# PrototypeBoardV2C.net
KiCad netlist of a schematic drawn in EasyEDA Pro
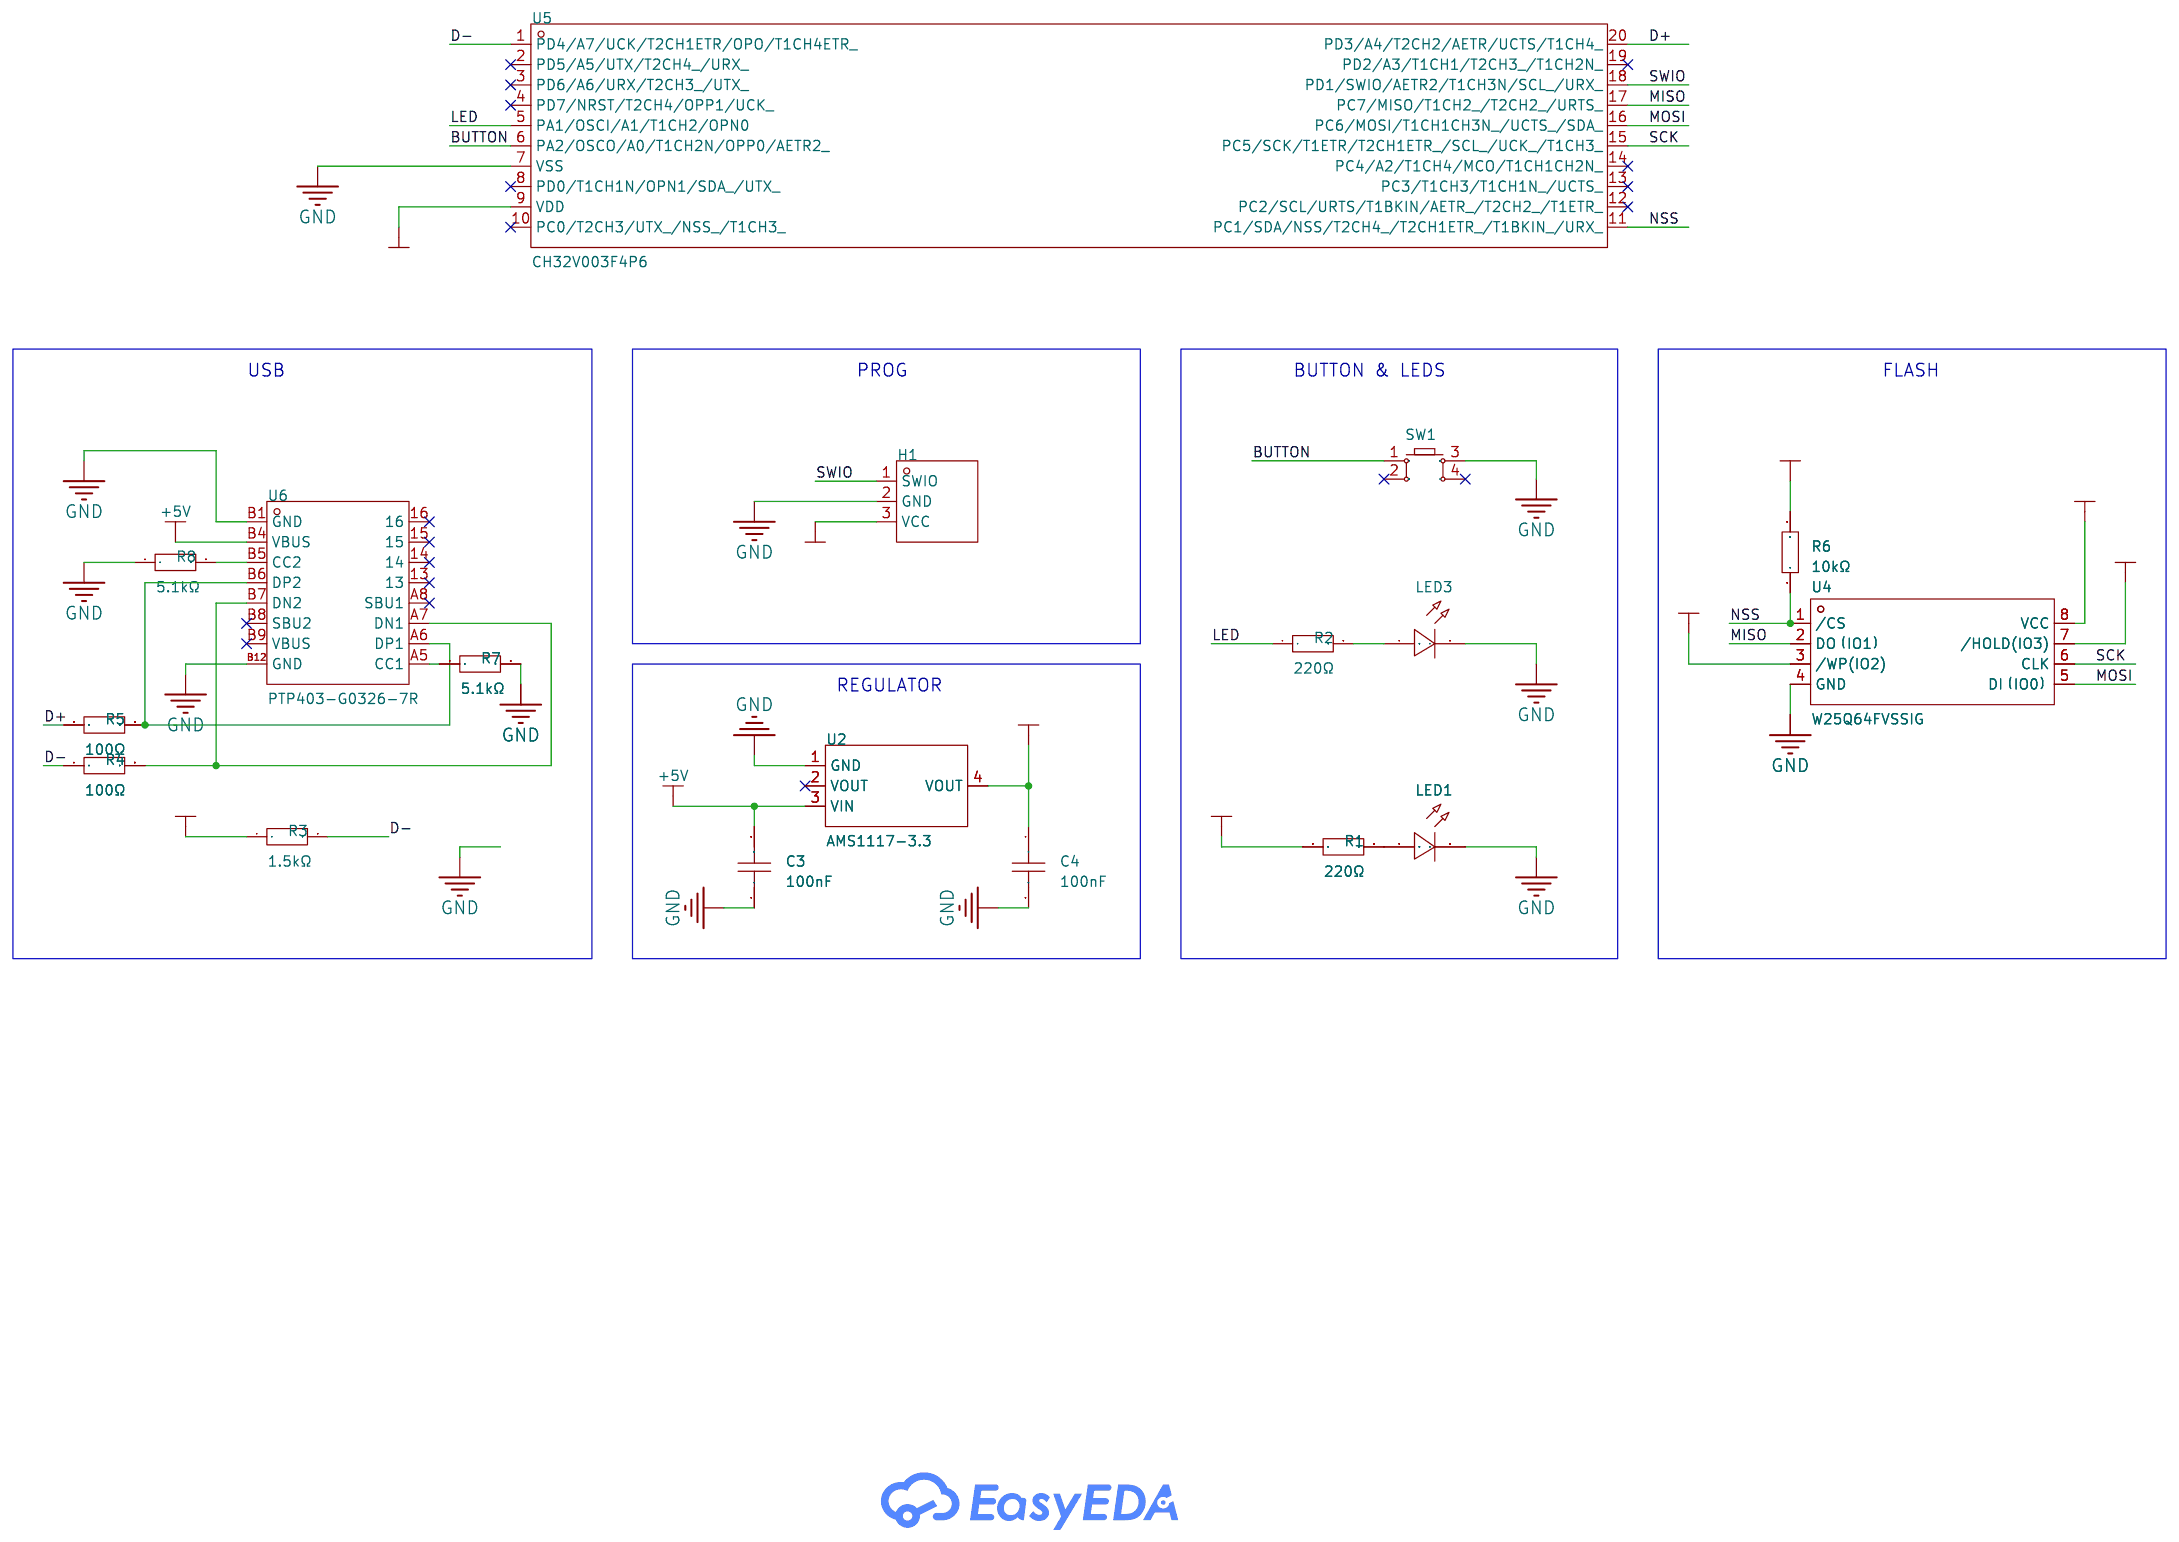
[diagram p0: schematic sheet]

(export (version "E")
  (design (tool "Eeschema 10.0.6"))
  (components
    (comp (ref "C3")
      (value "100nF")
      (footprint "easyedapro:CAP-TH_L5.8-W3.0-P4.7-D0.45")
      (fields (field (name "Manufacturer Part") "1C10Z5U104M050B") (field (name "Manufacturer") "VISHAY(威世)"))
      (libsource (lib "easyedapro") (part "1C10Z5U104M050B"))
    )
    (comp (ref "C4")
      (value "100nF")
      (footprint "easyedapro:CAP-TH_L5.8-W3.0-P4.7-D0.45")
      (fields (field (name "Manufacturer Part") "1C10Z5U104M050B") (field (name "Manufacturer") "VISHAY(威世)"))
      (libsource (lib "easyedapro") (part "1C10Z5U104M050B"))
    )
    (comp (ref "H1")
      (value "~")
      (footprint "easyedapro:HDR-TH_3P-P2.54-V-M")
      (libsource (lib "easyedapro") (part "PZ254V-11-03P_C2937625"))
    )
    (comp (ref "LED1")
      (value "~")
      (footprint "easyedapro:LED-TH_BD3.0-P2.54-FD")
      (libsource (lib "easyedapro") (part "LED_TH-R"))
    )
    (comp (ref "LED3")
      (value "~")
      (footprint "easyedapro:LED-TH_BD5.0-P2.54-L-RD_WHITE")
      (libsource (lib "easyedapro") (part "LED_TH-B"))
    )
    (comp (ref "R1")
      (value "220Ω")
      (footprint "easyedapro:RES-TH_BD1.8-L3.2-P7.20-D0.4")
      (libsource (lib "easyedapro") (part "Res"))
    )
    (comp (ref "R2")
      (value "220Ω")
      (footprint "easyedapro:RES-TH_BD1.8-L3.2-P7.20-D0.4")
      (libsource (lib "easyedapro") (part "Res"))
    )
    (comp (ref "R3")
      (value "1.5kΩ")
      (footprint "easyedapro:RES-TH_BD1.8-L3.2-P7.20-D0.4")
      (libsource (lib "easyedapro") (part "Res"))
    )
    (comp (ref "R4")
      (value "100Ω")
      (footprint "easyedapro:RES-TH_BD1.8-L3.2-P7.20-D0.4")
      (libsource (lib "easyedapro") (part "Res"))
    )
    (comp (ref "R5")
      (value "100Ω")
      (footprint "easyedapro:RES-TH_BD1.8-L3.2-P7.20-D0.4")
      (libsource (lib "easyedapro") (part "Res"))
    )
    (comp (ref "R6")
      (value "10kΩ")
      (footprint "easyedapro:RES-TH_BD1.8-L3.2-P7.20-D0.4")
      (libsource (lib "easyedapro") (part "Res"))
    )
    (comp (ref "R7")
      (value "5.1kΩ")
      (footprint "easyedapro:RES-TH_BD1.8-L3.2-P7.20-D0.4")
      (libsource (lib "easyedapro") (part "Res"))
    )
    (comp (ref "R8")
      (value "5.1kΩ")
      (footprint "easyedapro:RES-TH_BD1.8-L3.2-P7.20-D0.4")
      (libsource (lib "easyedapro") (part "Res"))
    )
    (comp (ref "SW1")
      (value "~")
      (footprint "easyedapro:KEY-TH_4P-L6.0-W6.0-P3.90-LS6.5")
      (libsource (lib "easyedapro") (part "轻触按键"))
    )
    (comp (ref "U2")
      (value "AMS1117-3.3")
      (footprint "easyedapro:SOT-223-3_L6.5-W3.4-P2.30-LS7.0-BR")
      (fields (field (name "Manufacturer") "AMS"))
      (libsource (lib "easyedapro") (part "AMS1117-3.3"))
    )
    (comp (ref "U4")
      (value "W25Q64FVSSIG")
      (footprint "easyedapro:SOIC-8_L5.3-W5.3-P1.27-LS8.0-BL")
      (libsource (lib "easyedapro") (part "W25Q64FVSSIG_C66141"))
    )
    (comp (ref "U5")
      (value "CH32V003F4P6")
      (footprint "easyedapro:TSSOP-20_L6.5-W4.4-P0.65-LS6.4-BL")
      (fields (field (name "Manufacturer") "WCH(南京沁恒)"))
      (libsource (lib "easyedapro") (part "CH32V003F4P6"))
    )
    (comp (ref "U6")
      (value "PTP403-G0326-7R")
      (footprint "easyedapro:USB-SMD_PTP403-G0326-7R")
      (libsource (lib "easyedapro") (part "PTP403-G0326-7R"))
    )
  )
  (nets
    (net (code "1") (name "+3.3V") (class "Default")
      (node (ref "C4") (pin "1") (pinfunction "1_1") (pintype "unspecified"))
      (node (ref "H1") (pin "3") (pinfunction "VCC_3") (pintype "unspecified"))
      (node (ref "R1") (pin "1") (pinfunction "1_1") (pintype "input"))
      (node (ref "R3") (pin "1") (pinfunction "1_1") (pintype "input"))
      (node (ref "R6") (pin "2") (pinfunction "2_2") (pintype "input"))
      (node (ref "U2") (pin "4") (pinfunction "VOUT_4") (pintype "unspecified"))
      (node (ref "U4") (pin "3") (pinfunction "/WP(IO2)_3") (pintype "unspecified"))
      (node (ref "U4") (pin "7") (pinfunction "/HOLD(IO3)_7") (pintype "unspecified"))
      (node (ref "U4") (pin "8") (pinfunction "VCC_8") (pintype "unspecified"))
      (node (ref "U5") (pin "9") (pinfunction "VDD_9") (pintype "unspecified"))
    )
    (net (code "2") (name "+5V") (class "Default")
      (node (ref "C3") (pin "2") (pinfunction "2_2") (pintype "unspecified"))
      (node (ref "U2") (pin "3") (pinfunction "VIN_3") (pintype "unspecified"))
      (node (ref "U6") (pin "B4") (pinfunction "VBUS_B4") (pintype "input"))
    )
    (net (code "3") (name "/BUTTON") (class "Default")
      (node (ref "SW1") (pin "1") (pinfunction "1_1") (pintype "input"))
      (node (ref "U5") (pin "6") (pinfunction "PA2/OSCO/A0/T1CH2N/OPP0/AETR2__6") (pintype "unspecified"))
    )
    (net (code "4") (name "/D+") (class "Default")
      (node (ref "R5") (pin "1") (pinfunction "1_1") (pintype "input"))
      (node (ref "U5") (pin "20") (pinfunction "PD3/A4/T2CH2/AETR/UCTS/T1CH4__20") (pintype "unspecified"))
    )
    (net (code "5") (name "/D-") (class "Default")
      (node (ref "R3") (pin "2") (pinfunction "2_2") (pintype "input"))
      (node (ref "R4") (pin "1") (pinfunction "1_1") (pintype "input"))
      (node (ref "U5") (pin "1") (pinfunction "PD4/A7/UCK/T2CH1ETR/OPO/T1CH4ETR__1") (pintype "unspecified"))
    )
    (net (code "6") (name "/LED") (class "Default")
      (node (ref "R2") (pin "1") (pinfunction "1_1") (pintype "input"))
      (node (ref "U5") (pin "5") (pinfunction "PA1/OSCI/A1/T1CH2/OPN0_5") (pintype "unspecified"))
    )
    (net (code "7") (name "/MISO") (class "Default")
      (node (ref "U4") (pin "2") (pinfunction "DO（IO1）_2") (pintype "unspecified"))
      (node (ref "U5") (pin "17") (pinfunction "PC7/MISO/T1CH2_/T2CH2_/URTS__17") (pintype "unspecified"))
    )
    (net (code "8") (name "/MOSI") (class "Default")
      (node (ref "U4") (pin "5") (pinfunction "DI（IO0）_5") (pintype "unspecified"))
      (node (ref "U5") (pin "16") (pinfunction "PC6/MOSI/T1CH1CH3N_/UCTS_/SDA__16") (pintype "unspecified"))
    )
    (net (code "9") (name "/NSS") (class "Default")
      (node (ref "R6") (pin "1") (pinfunction "1_1") (pintype "input"))
      (node (ref "U4") (pin "1") (pinfunction "/CS_1") (pintype "unspecified"))
      (node (ref "U5") (pin "11") (pinfunction "PC1/SDA/NSS/T2CH4_/T2CH1ETR_/T1BKIN_/URX__11") (pintype "unspecified"))
    )
    (net (code "10") (name "/SCK") (class "Default")
      (node (ref "U4") (pin "6") (pinfunction "CLK_6") (pintype "unspecified"))
      (node (ref "U5") (pin "15") (pinfunction "PC5/SCK/T1ETR/T2CH1ETR_/SCL_/UCK_/T1CH3__15") (pintype "unspecified"))
    )
    (net (code "11") (name "/SWIO") (class "Default")
      (node (ref "H1") (pin "1") (pinfunction "SWIO_1") (pintype "unspecified"))
      (node (ref "U5") (pin "18") (pinfunction "PD1/SWIO/AETR2/T1CH3N/SCL_/URX__18") (pintype "unspecified"))
    )
    (net (code "12") (name "GND") (class "Default")
      (node (ref "C3") (pin "1") (pinfunction "1_1") (pintype "unspecified"))
      (node (ref "C4") (pin "2") (pinfunction "2_2") (pintype "unspecified"))
      (node (ref "H1") (pin "2") (pinfunction "GND_2") (pintype "unspecified"))
      (node (ref "LED1") (pin "2") (pinfunction "A_2") (pintype "input"))
      (node (ref "LED3") (pin "2") (pinfunction "A_2") (pintype "input"))
      (node (ref "R7") (pin "2") (pinfunction "2_2") (pintype "input"))
      (node (ref "R8") (pin "1") (pinfunction "1_1") (pintype "input"))
      (node (ref "SW1") (pin "3") (pinfunction "3_3") (pintype "input"))
      (node (ref "U2") (pin "1") (pinfunction "GND_1") (pintype "unspecified"))
      (node (ref "U4") (pin "4") (pinfunction "GND_4") (pintype "unspecified"))
      (node (ref "U5") (pin "7") (pinfunction "VSS_7") (pintype "unspecified"))
      (node (ref "U6") (pin "B1") (pinfunction "GND_B1") (pintype "input"))
      (node (ref "U6") (pin "B12") (pinfunction "GND_B12") (pintype "input"))
    )
    (net (code "13") (name "Net-(LED1-C)") (class "Default")
      (node (ref "LED1") (pin "1") (pinfunction "C_1") (pintype "input"))
      (node (ref "R1") (pin "2") (pinfunction "2_2") (pintype "input"))
    )
    (net (code "14") (name "Net-(LED3-C)") (class "Default")
      (node (ref "LED3") (pin "1") (pinfunction "C_1") (pintype "input"))
      (node (ref "R2") (pin "2") (pinfunction "2_2") (pintype "input"))
    )
    (net (code "15") (name "Net-(U6-CC1)") (class "Default")
      (node (ref "R7") (pin "1") (pinfunction "1_1") (pintype "input"))
      (node (ref "U6") (pin "A5") (pinfunction "CC1_A5") (pintype "input"))
    )
    (net (code "16") (name "Net-(U6-CC2)") (class "Default")
      (node (ref "R8") (pin "2") (pinfunction "2_2") (pintype "input"))
      (node (ref "U6") (pin "B5") (pinfunction "CC2_B5") (pintype "input"))
    )
    (net (code "17") (name "Net-(U6-DN1)") (class "Default")
      (node (ref "R4") (pin "2") (pinfunction "2_2") (pintype "input"))
      (node (ref "U6") (pin "A7") (pinfunction "DN1_A7") (pintype "input"))
      (node (ref "U6") (pin "B7") (pinfunction "DN2_B7") (pintype "input"))
    )
    (net (code "18") (name "Net-(U6-DP1)") (class "Default")
      (node (ref "R5") (pin "2") (pinfunction "2_2") (pintype "input"))
      (node (ref "U6") (pin "A6") (pinfunction "DP1_A6") (pintype "input"))
      (node (ref "U6") (pin "B6") (pinfunction "DP2_B6") (pintype "input"))
    )
    (net (code "19") (name "unconnected-(SW1-Pad2)") (class "Default")
      (node (ref "SW1") (pin "2") (pinfunction "2_2") (pintype "input+no_connect"))
    )
    (net (code "20") (name "unconnected-(SW1-Pad4)") (class "Default")
      (node (ref "SW1") (pin "4") (pinfunction "4_4") (pintype "input+no_connect"))
    )
    (net (code "21") (name "unconnected-(U2-VOUT-Pad2)") (class "Default")
      (node (ref "U2") (pin "2") (pinfunction "VOUT_2") (pintype "unspecified+no_connect"))
    )
    (net (code "22") (name "unconnected-(U5-PC0{slash}T2CH3{slash}UTX_{slash}NSS_{slash}T1CH3_-Pad10)") (class "Default")
      (node (ref "U5") (pin "10") (pinfunction "PC0/T2CH3/UTX_/NSS_/T1CH3__10") (pintype "unspecified+no_connect"))
    )
    (net (code "23") (name "unconnected-(U5-PC2{slash}SCL{slash}URTS{slash}T1BKIN{slash}AETR_{slash}T2CH2_{slash}T1ETR_-Pad12)") (class "Default")
      (node (ref "U5") (pin "12") (pinfunction "PC2/SCL/URTS/T1BKIN/AETR_/T2CH2_/T1ETR__12") (pintype "unspecified+no_connect"))
    )
    (net (code "24") (name "unconnected-(U5-PC3{slash}T1CH3{slash}T1CH1N_{slash}UCTS_-Pad13)") (class "Default")
      (node (ref "U5") (pin "13") (pinfunction "PC3/T1CH3/T1CH1N_/UCTS__13") (pintype "unspecified+no_connect"))
    )
    (net (code "25") (name "unconnected-(U5-PC4{slash}A2{slash}T1CH4{slash}MCO{slash}T1CH1CH2N_-Pad14)") (class "Default")
      (node (ref "U5") (pin "14") (pinfunction "PC4/A2/T1CH4/MCO/T1CH1CH2N__14") (pintype "unspecified+no_connect"))
    )
    (net (code "26") (name "unconnected-(U5-PD0{slash}T1CH1N{slash}OPN1{slash}SDA_{slash}UTX_-Pad8)") (class "Default")
      (node (ref "U5") (pin "8") (pinfunction "PD0/T1CH1N/OPN1/SDA_/UTX__8") (pintype "unspecified+no_connect"))
    )
    (net (code "27") (name "unconnected-(U5-PD2{slash}A3{slash}T1CH1{slash}T2CH3_{slash}T1CH2N_-Pad19)") (class "Default")
      (node (ref "U5") (pin "19") (pinfunction "PD2/A3/T1CH1/T2CH3_/T1CH2N__19") (pintype "unspecified+no_connect"))
    )
    (net (code "28") (name "unconnected-(U5-PD5{slash}A5{slash}UTX{slash}T2CH4_{slash}URX_-Pad2)") (class "Default")
      (node (ref "U5") (pin "2") (pinfunction "PD5/A5/UTX/T2CH4_/URX__2") (pintype "unspecified+no_connect"))
    )
    (net (code "29") (name "unconnected-(U5-PD6{slash}A6{slash}URX{slash}T2CH3_{slash}UTX_-Pad3)") (class "Default")
      (node (ref "U5") (pin "3") (pinfunction "PD6/A6/URX/T2CH3_/UTX__3") (pintype "unspecified+no_connect"))
    )
    (net (code "30") (name "unconnected-(U5-PD7{slash}NRST{slash}T2CH4{slash}OPP1{slash}UCK_-Pad4)") (class "Default")
      (node (ref "U5") (pin "4") (pinfunction "PD7/NRST/T2CH4/OPP1/UCK__4") (pintype "unspecified+no_connect"))
    )
    (net (code "31") (name "unconnected-(U6-Pad13)") (class "Default")
      (node (ref "U6") (pin "13") (pinfunction "13_13") (pintype "input+no_connect"))
    )
    (net (code "32") (name "unconnected-(U6-Pad14)") (class "Default")
      (node (ref "U6") (pin "14") (pinfunction "14_14") (pintype "input+no_connect"))
    )
    (net (code "33") (name "unconnected-(U6-Pad15)") (class "Default")
      (node (ref "U6") (pin "15") (pinfunction "15_15") (pintype "input+no_connect"))
    )
    (net (code "34") (name "unconnected-(U6-Pad16)") (class "Default")
      (node (ref "U6") (pin "16") (pinfunction "16_16") (pintype "input+no_connect"))
    )
    (net (code "35") (name "unconnected-(U6-SBU1-PadA8)") (class "Default")
      (node (ref "U6") (pin "A8") (pinfunction "SBU1_A8") (pintype "input+no_connect"))
    )
    (net (code "36") (name "unconnected-(U6-SBU2-PadB8)") (class "Default")
      (node (ref "U6") (pin "B8") (pinfunction "SBU2_B8") (pintype "input+no_connect"))
    )
    (net (code "37") (name "unconnected-(U6-VBUS-PadB9)") (class "Default")
      (node (ref "U6") (pin "B9") (pinfunction "VBUS_B9") (pintype "input+no_connect"))
    )
  )
)
